# SCH_Capstone_2024-02-12.net
KiCad netlist of a schematic drawn in EasyEDA
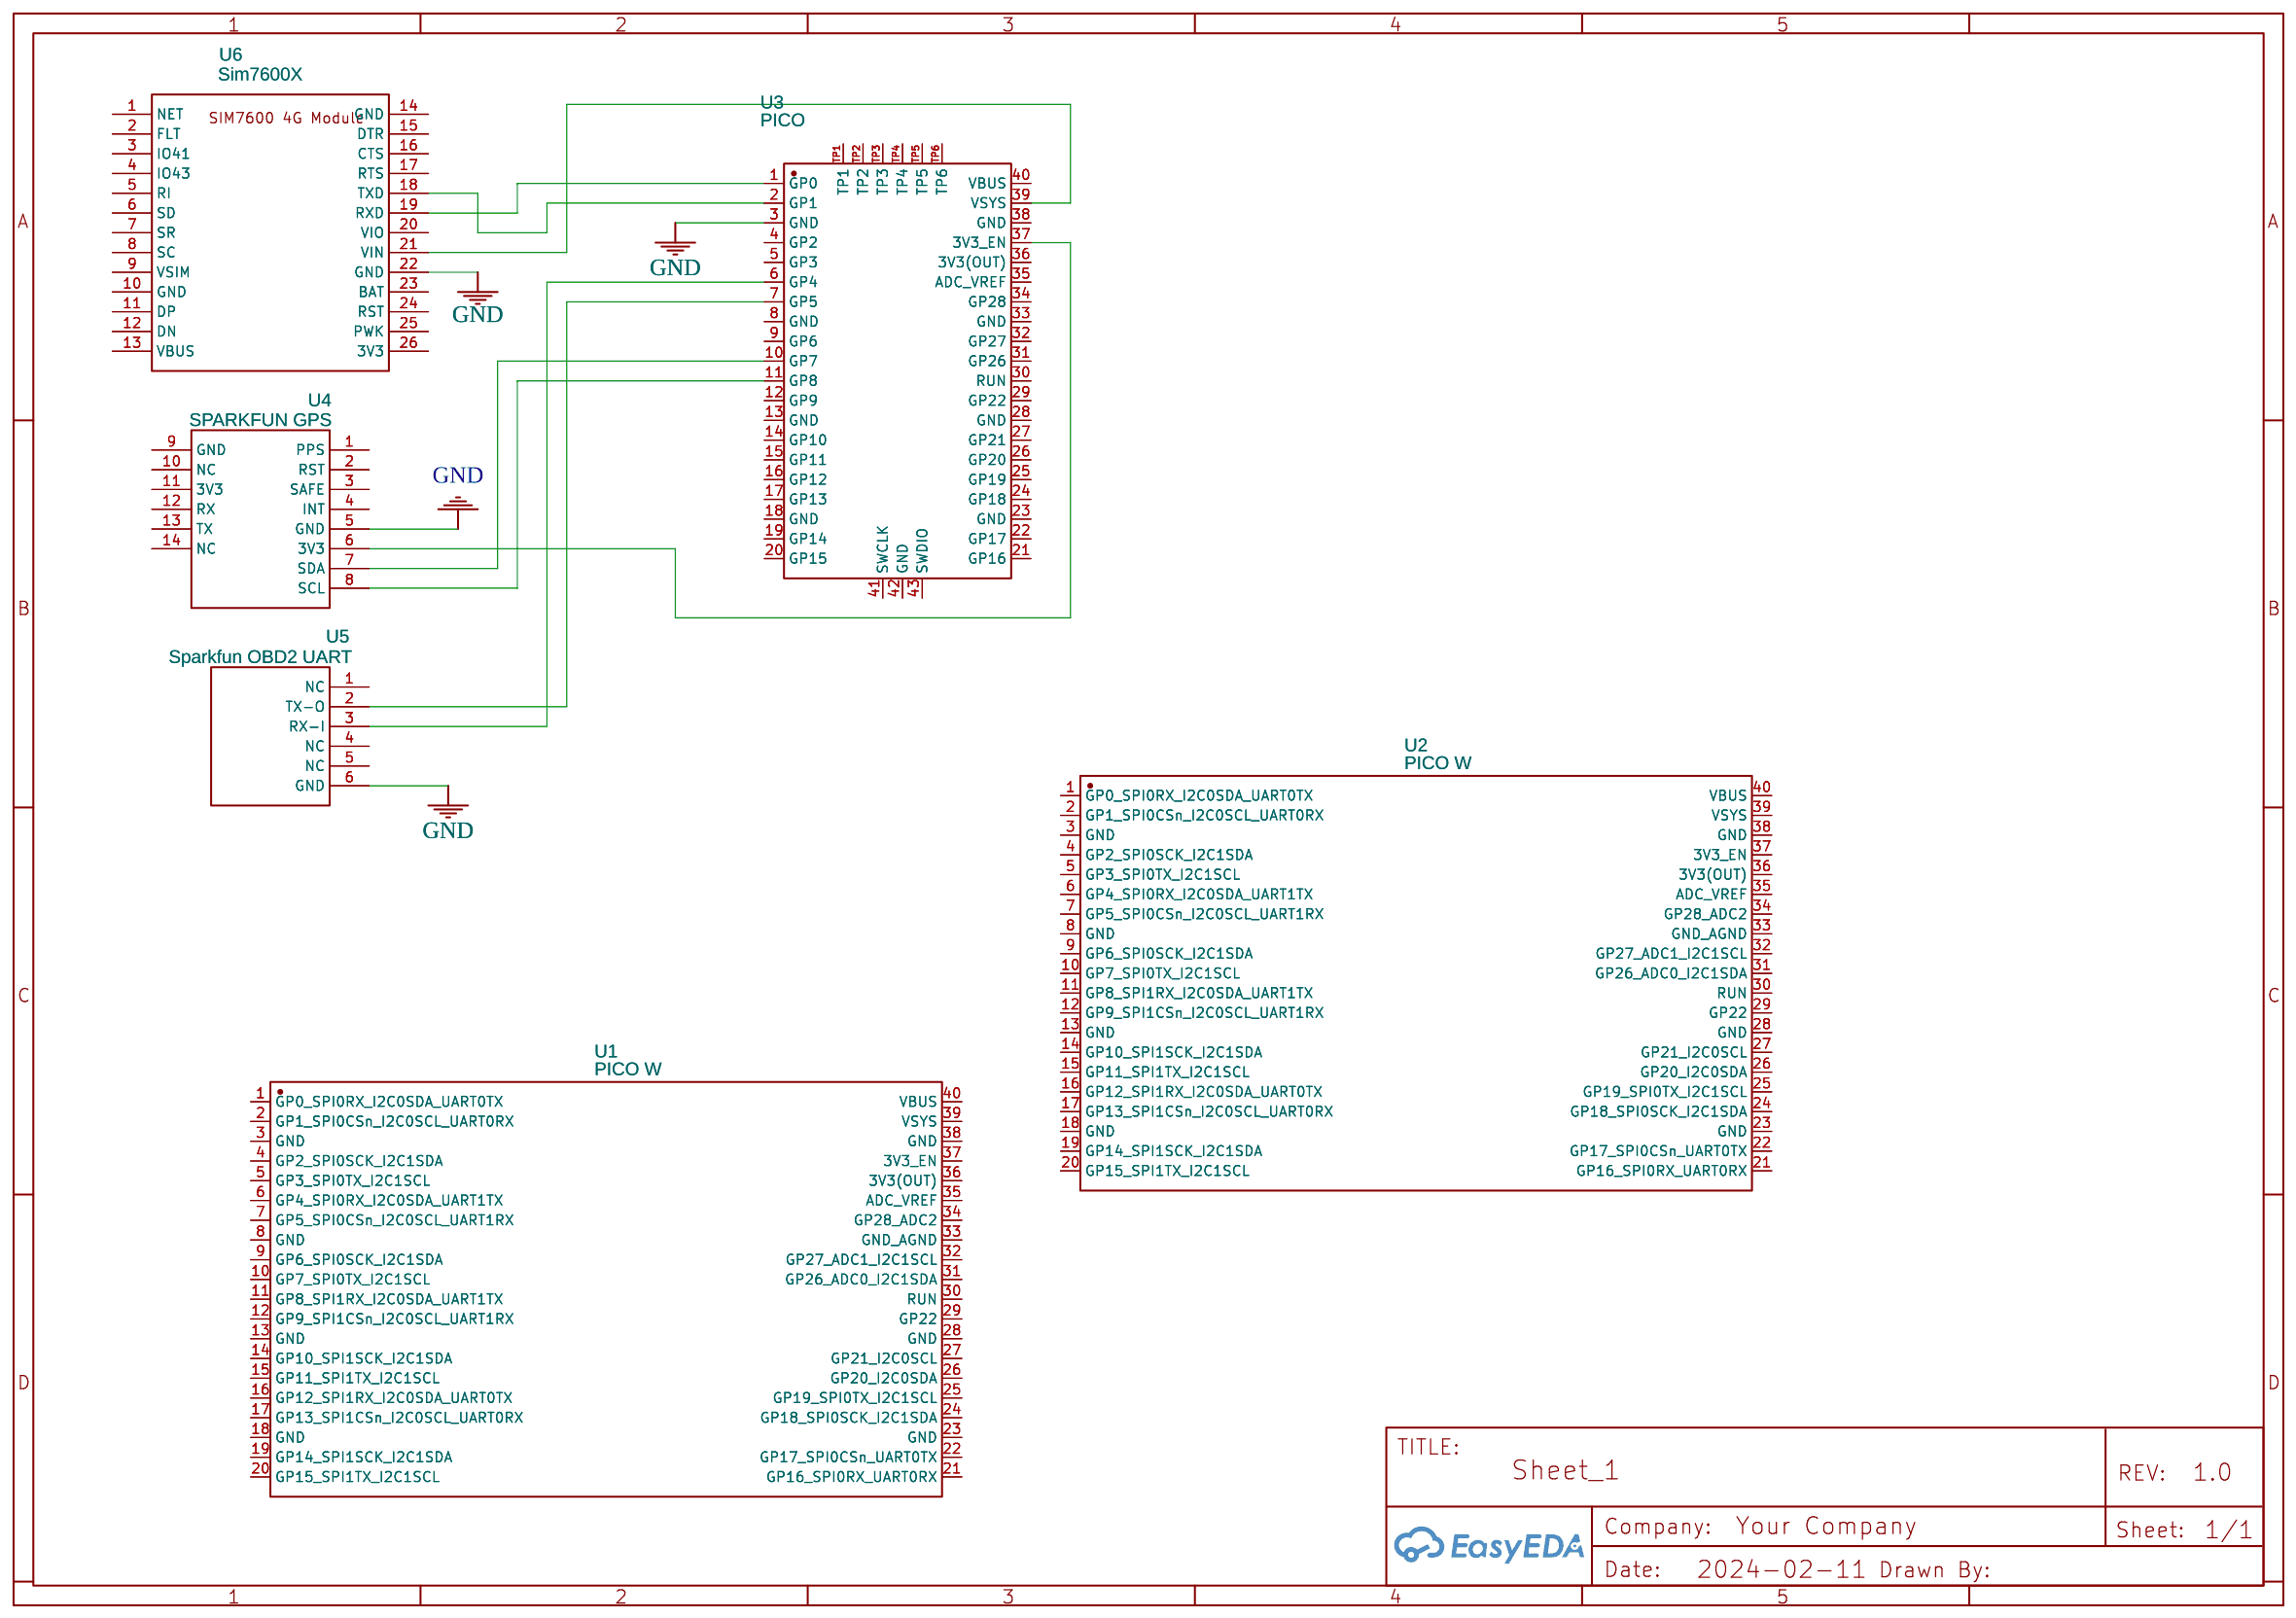
[diagram p0: schematic sheet]

(export (version "E")
  (design (tool "Eeschema 10.0.6"))
  (components
    (comp (ref "U1")
      (value "PICO W")
      (fields (field (name "Manufacturer") "Raspberry Pi(树莓派)"))
      (libsource (lib "") (part "PICO W"))
    )
    (comp (ref "U2")
      (value "PICO W")
      (fields (field (name "Manufacturer") "Raspberry Pi(树莓派)"))
      (libsource (lib "") (part "PICO W"))
    )
    (comp (ref "U3")
      (value "PICO")
      (fields (field (name "Manufacturer") "Raspberry Pi(树莓派)"))
      (libsource (lib "") (part "PICO"))
    )
    (comp (ref "U4") (value "SPARKFUN GPS") (libsource (lib "") (part "SPARKFUN GPS")))
    (comp (ref "U5") (value "Sparkfun OBD2 UART") (libsource (lib "") (part "Sparkfun OBD2 UART")))
    (comp (ref "U6") (value "Sim7600X") (libsource (lib "") (part "Sim7600X")))
  )
  (nets
    (net (code "1") (name "GND") (class "Default")
      (node (ref "U3") (pin "3") (pinfunction "GND_3") (pintype "unspecified"))
      (node (ref "U4") (pin "5") (pinfunction "GND_5") (pintype "unspecified"))
      (node (ref "U5") (pin "6") (pinfunction "GND_6") (pintype "unspecified"))
      (node (ref "U6") (pin "22") (pinfunction "GND_22") (pintype "unspecified"))
    )
    (net (code "2") (name "Net-(U3-3V3_EN)") (class "Default")
      (node (ref "U3") (pin "37") (pinfunction "3V3_EN_37") (pintype "unspecified"))
      (node (ref "U4") (pin "6") (pinfunction "3V3_6") (pintype "unspecified"))
    )
    (net (code "3") (name "Net-(U3-GP0)") (class "Default")
      (node (ref "U3") (pin "1") (pinfunction "GP0_1") (pintype "unspecified"))
      (node (ref "U6") (pin "19") (pinfunction "RXD_19") (pintype "unspecified"))
    )
    (net (code "4") (name "Net-(U3-GP1)") (class "Default")
      (node (ref "U3") (pin "2") (pinfunction "GP1_2") (pintype "unspecified"))
      (node (ref "U6") (pin "18") (pinfunction "TXD_18") (pintype "unspecified"))
    )
    (net (code "5") (name "Net-(U3-GP4)") (class "Default")
      (node (ref "U3") (pin "6") (pinfunction "GP4_6") (pintype "unspecified"))
      (node (ref "U5") (pin "3") (pinfunction "RX-I_3") (pintype "unspecified"))
    )
    (net (code "6") (name "Net-(U3-GP5)") (class "Default")
      (node (ref "U3") (pin "7") (pinfunction "GP5_7") (pintype "unspecified"))
      (node (ref "U5") (pin "2") (pinfunction "TX-O_2") (pintype "unspecified"))
    )
    (net (code "7") (name "Net-(U3-GP7)") (class "Default")
      (node (ref "U3") (pin "10") (pinfunction "GP7_10") (pintype "unspecified"))
      (node (ref "U4") (pin "7") (pinfunction "SDA_7") (pintype "unspecified"))
    )
    (net (code "8") (name "Net-(U3-GP8)") (class "Default")
      (node (ref "U3") (pin "11") (pinfunction "GP8_11") (pintype "unspecified"))
      (node (ref "U4") (pin "8") (pinfunction "SCL_8") (pintype "unspecified"))
    )
    (net (code "9") (name "Net-(U3-VSYS)") (class "Default")
      (node (ref "U3") (pin "39") (pinfunction "VSYS_39") (pintype "unspecified"))
      (node (ref "U6") (pin "21") (pinfunction "VIN_21") (pintype "unspecified"))
    )
    (net (code "10") (name "unconnected-(U1-3V3(OUT)-Pad36)") (class "Default")
      (node (ref "U1") (pin "36") (pinfunction "3V3(OUT)_36") (pintype "unspecified"))
    )
    (net (code "11") (name "unconnected-(U1-3V3_EN-Pad37)") (class "Default")
      (node (ref "U1") (pin "37") (pinfunction "3V3_EN_37") (pintype "unspecified"))
    )
    (net (code "12") (name "unconnected-(U1-ADC_VREF-Pad35)") (class "Default")
      (node (ref "U1") (pin "35") (pinfunction "ADC_VREF_35") (pintype "unspecified"))
    )
    (net (code "13") (name "unconnected-(U1-GND-Pad3)") (class "Default")
      (node (ref "U1") (pin "3") (pinfunction "GND_3") (pintype "unspecified"))
    )
    (net (code "14") (name "unconnected-(U1-GND-Pad8)") (class "Default")
      (node (ref "U1") (pin "8") (pinfunction "GND_8") (pintype "unspecified"))
    )
    (net (code "15") (name "unconnected-(U1-GND-Pad13)") (class "Default")
      (node (ref "U1") (pin "13") (pinfunction "GND_13") (pintype "unspecified"))
    )
    (net (code "16") (name "unconnected-(U1-GND-Pad18)") (class "Default")
      (node (ref "U1") (pin "18") (pinfunction "GND_18") (pintype "unspecified"))
    )
    (net (code "17") (name "unconnected-(U1-GND-Pad23)") (class "Default")
      (node (ref "U1") (pin "23") (pinfunction "GND_23") (pintype "unspecified"))
    )
    (net (code "18") (name "unconnected-(U1-GND-Pad28)") (class "Default")
      (node (ref "U1") (pin "28") (pinfunction "GND_28") (pintype "unspecified"))
    )
    (net (code "19") (name "unconnected-(U1-GND-Pad38)") (class "Default")
      (node (ref "U1") (pin "38") (pinfunction "GND_38") (pintype "unspecified"))
    )
    (net (code "20") (name "unconnected-(U1-GND_AGND-Pad33)") (class "Default")
      (node (ref "U1") (pin "33") (pinfunction "GND_AGND_33") (pintype "unspecified"))
    )
    (net (code "21") (name "unconnected-(U1-GP0_SPI0RX_I2C0SDA_UART0TX-Pad1)") (class "Default")
      (node (ref "U1") (pin "1") (pinfunction "GP0_SPI0RX_I2C0SDA_UART0TX_1") (pintype "unspecified"))
    )
    (net (code "22") (name "unconnected-(U1-GP1_SPI0CSn_I2C0SCL_UART0RX-Pad2)") (class "Default")
      (node (ref "U1") (pin "2") (pinfunction "GP1_SPI0CSn_I2C0SCL_UART0RX_2") (pintype "unspecified"))
    )
    (net (code "23") (name "unconnected-(U1-GP2_SPI0SCK_I2C1SDA-Pad4)") (class "Default")
      (node (ref "U1") (pin "4") (pinfunction "GP2_SPI0SCK_I2C1SDA_4") (pintype "unspecified"))
    )
    (net (code "24") (name "unconnected-(U1-GP3_SPI0TX_I2C1SCL-Pad5)") (class "Default")
      (node (ref "U1") (pin "5") (pinfunction "GP3_SPI0TX_I2C1SCL_5") (pintype "unspecified"))
    )
    (net (code "25") (name "unconnected-(U1-GP4_SPI0RX_I2C0SDA_UART1TX-Pad6)") (class "Default")
      (node (ref "U1") (pin "6") (pinfunction "GP4_SPI0RX_I2C0SDA_UART1TX_6") (pintype "unspecified"))
    )
    (net (code "26") (name "unconnected-(U1-GP5_SPI0CSn_I2C0SCL_UART1RX-Pad7)") (class "Default")
      (node (ref "U1") (pin "7") (pinfunction "GP5_SPI0CSn_I2C0SCL_UART1RX_7") (pintype "unspecified"))
    )
    (net (code "27") (name "unconnected-(U1-GP6_SPI0SCK_I2C1SDA-Pad9)") (class "Default")
      (node (ref "U1") (pin "9") (pinfunction "GP6_SPI0SCK_I2C1SDA_9") (pintype "unspecified"))
    )
    (net (code "28") (name "unconnected-(U1-GP7_SPI0TX_I2C1SCL-Pad10)") (class "Default")
      (node (ref "U1") (pin "10") (pinfunction "GP7_SPI0TX_I2C1SCL_10") (pintype "unspecified"))
    )
    (net (code "29") (name "unconnected-(U1-GP8_SPI1RX_I2C0SDA_UART1TX-Pad11)") (class "Default")
      (node (ref "U1") (pin "11") (pinfunction "GP8_SPI1RX_I2C0SDA_UART1TX_11") (pintype "unspecified"))
    )
    (net (code "30") (name "unconnected-(U1-GP9_SPI1CSn_I2C0SCL_UART1RX-Pad12)") (class "Default")
      (node (ref "U1") (pin "12") (pinfunction "GP9_SPI1CSn_I2C0SCL_UART1RX_12") (pintype "unspecified"))
    )
    (net (code "31") (name "unconnected-(U1-GP10_SPI1SCK_I2C1SDA-Pad14)") (class "Default")
      (node (ref "U1") (pin "14") (pinfunction "GP10_SPI1SCK_I2C1SDA_14") (pintype "unspecified"))
    )
    (net (code "32") (name "unconnected-(U1-GP11_SPI1TX_I2C1SCL-Pad15)") (class "Default")
      (node (ref "U1") (pin "15") (pinfunction "GP11_SPI1TX_I2C1SCL_15") (pintype "unspecified"))
    )
    (net (code "33") (name "unconnected-(U1-GP12_SPI1RX_I2C0SDA_UART0TX-Pad16)") (class "Default")
      (node (ref "U1") (pin "16") (pinfunction "GP12_SPI1RX_I2C0SDA_UART0TX_16") (pintype "unspecified"))
    )
    (net (code "34") (name "unconnected-(U1-GP13_SPI1CSn_I2C0SCL_UART0RX-Pad17)") (class "Default")
      (node (ref "U1") (pin "17") (pinfunction "GP13_SPI1CSn_I2C0SCL_UART0RX_17") (pintype "unspecified"))
    )
    (net (code "35") (name "unconnected-(U1-GP14_SPI1SCK_I2C1SDA-Pad19)") (class "Default")
      (node (ref "U1") (pin "19") (pinfunction "GP14_SPI1SCK_I2C1SDA_19") (pintype "unspecified"))
    )
    (net (code "36") (name "unconnected-(U1-GP15_SPI1TX_I2C1SCL-Pad20)") (class "Default")
      (node (ref "U1") (pin "20") (pinfunction "GP15_SPI1TX_I2C1SCL_20") (pintype "unspecified"))
    )
    (net (code "37") (name "unconnected-(U1-GP16_SPI0RX_UART0RX-Pad21)") (class "Default")
      (node (ref "U1") (pin "21") (pinfunction "GP16_SPI0RX_UART0RX_21") (pintype "unspecified"))
    )
    (net (code "38") (name "unconnected-(U1-GP17_SPI0CSn_UART0TX-Pad22)") (class "Default")
      (node (ref "U1") (pin "22") (pinfunction "GP17_SPI0CSn_UART0TX_22") (pintype "unspecified"))
    )
    (net (code "39") (name "unconnected-(U1-GP18_SPI0SCK_I2C1SDA-Pad24)") (class "Default")
      (node (ref "U1") (pin "24") (pinfunction "GP18_SPI0SCK_I2C1SDA_24") (pintype "unspecified"))
    )
    (net (code "40") (name "unconnected-(U1-GP19_SPI0TX_I2C1SCL-Pad25)") (class "Default")
      (node (ref "U1") (pin "25") (pinfunction "GP19_SPI0TX_I2C1SCL_25") (pintype "unspecified"))
    )
    (net (code "41") (name "unconnected-(U1-GP20_I2C0SDA-Pad26)") (class "Default")
      (node (ref "U1") (pin "26") (pinfunction "GP20_I2C0SDA_26") (pintype "unspecified"))
    )
    (net (code "42") (name "unconnected-(U1-GP21_I2C0SCL-Pad27)") (class "Default")
      (node (ref "U1") (pin "27") (pinfunction "GP21_I2C0SCL_27") (pintype "unspecified"))
    )
    (net (code "43") (name "unconnected-(U1-GP22-Pad29)") (class "Default")
      (node (ref "U1") (pin "29") (pinfunction "GP22_29") (pintype "unspecified"))
    )
    (net (code "44") (name "unconnected-(U1-GP26_ADC0_I2C1SDA-Pad31)") (class "Default")
      (node (ref "U1") (pin "31") (pinfunction "GP26_ADC0_I2C1SDA_31") (pintype "unspecified"))
    )
    (net (code "45") (name "unconnected-(U1-GP27_ADC1_I2C1SCL-Pad32)") (class "Default")
      (node (ref "U1") (pin "32") (pinfunction "GP27_ADC1_I2C1SCL_32") (pintype "unspecified"))
    )
    (net (code "46") (name "unconnected-(U1-GP28_ADC2-Pad34)") (class "Default")
      (node (ref "U1") (pin "34") (pinfunction "GP28_ADC2_34") (pintype "unspecified"))
    )
    (net (code "47") (name "unconnected-(U1-RUN-Pad30)") (class "Default")
      (node (ref "U1") (pin "30") (pinfunction "RUN_30") (pintype "unspecified"))
    )
    (net (code "48") (name "unconnected-(U1-VBUS-Pad40)") (class "Default")
      (node (ref "U1") (pin "40") (pinfunction "VBUS_40") (pintype "unspecified"))
    )
    (net (code "49") (name "unconnected-(U1-VSYS-Pad39)") (class "Default")
      (node (ref "U1") (pin "39") (pinfunction "VSYS_39") (pintype "unspecified"))
    )
    (net (code "50") (name "unconnected-(U2-3V3(OUT)-Pad36)") (class "Default")
      (node (ref "U2") (pin "36") (pinfunction "3V3(OUT)_36") (pintype "unspecified"))
    )
    (net (code "51") (name "unconnected-(U2-3V3_EN-Pad37)") (class "Default")
      (node (ref "U2") (pin "37") (pinfunction "3V3_EN_37") (pintype "unspecified"))
    )
    (net (code "52") (name "unconnected-(U2-ADC_VREF-Pad35)") (class "Default")
      (node (ref "U2") (pin "35") (pinfunction "ADC_VREF_35") (pintype "unspecified"))
    )
    (net (code "53") (name "unconnected-(U2-GND-Pad3)") (class "Default")
      (node (ref "U2") (pin "3") (pinfunction "GND_3") (pintype "unspecified"))
    )
    (net (code "54") (name "unconnected-(U2-GND-Pad8)") (class "Default")
      (node (ref "U2") (pin "8") (pinfunction "GND_8") (pintype "unspecified"))
    )
    (net (code "55") (name "unconnected-(U2-GND-Pad13)") (class "Default")
      (node (ref "U2") (pin "13") (pinfunction "GND_13") (pintype "unspecified"))
    )
    (net (code "56") (name "unconnected-(U2-GND-Pad18)") (class "Default")
      (node (ref "U2") (pin "18") (pinfunction "GND_18") (pintype "unspecified"))
    )
    (net (code "57") (name "unconnected-(U2-GND-Pad23)") (class "Default")
      (node (ref "U2") (pin "23") (pinfunction "GND_23") (pintype "unspecified"))
    )
    (net (code "58") (name "unconnected-(U2-GND-Pad28)") (class "Default")
      (node (ref "U2") (pin "28") (pinfunction "GND_28") (pintype "unspecified"))
    )
    (net (code "59") (name "unconnected-(U2-GND-Pad38)") (class "Default")
      (node (ref "U2") (pin "38") (pinfunction "GND_38") (pintype "unspecified"))
    )
    (net (code "60") (name "unconnected-(U2-GND_AGND-Pad33)") (class "Default")
      (node (ref "U2") (pin "33") (pinfunction "GND_AGND_33") (pintype "unspecified"))
    )
    (net (code "61") (name "unconnected-(U2-GP0_SPI0RX_I2C0SDA_UART0TX-Pad1)") (class "Default")
      (node (ref "U2") (pin "1") (pinfunction "GP0_SPI0RX_I2C0SDA_UART0TX_1") (pintype "unspecified"))
    )
    (net (code "62") (name "unconnected-(U2-GP1_SPI0CSn_I2C0SCL_UART0RX-Pad2)") (class "Default")
      (node (ref "U2") (pin "2") (pinfunction "GP1_SPI0CSn_I2C0SCL_UART0RX_2") (pintype "unspecified"))
    )
    (net (code "63") (name "unconnected-(U2-GP2_SPI0SCK_I2C1SDA-Pad4)") (class "Default")
      (node (ref "U2") (pin "4") (pinfunction "GP2_SPI0SCK_I2C1SDA_4") (pintype "unspecified"))
    )
    (net (code "64") (name "unconnected-(U2-GP3_SPI0TX_I2C1SCL-Pad5)") (class "Default")
      (node (ref "U2") (pin "5") (pinfunction "GP3_SPI0TX_I2C1SCL_5") (pintype "unspecified"))
    )
    (net (code "65") (name "unconnected-(U2-GP4_SPI0RX_I2C0SDA_UART1TX-Pad6)") (class "Default")
      (node (ref "U2") (pin "6") (pinfunction "GP4_SPI0RX_I2C0SDA_UART1TX_6") (pintype "unspecified"))
    )
    (net (code "66") (name "unconnected-(U2-GP5_SPI0CSn_I2C0SCL_UART1RX-Pad7)") (class "Default")
      (node (ref "U2") (pin "7") (pinfunction "GP5_SPI0CSn_I2C0SCL_UART1RX_7") (pintype "unspecified"))
    )
    (net (code "67") (name "unconnected-(U2-GP6_SPI0SCK_I2C1SDA-Pad9)") (class "Default")
      (node (ref "U2") (pin "9") (pinfunction "GP6_SPI0SCK_I2C1SDA_9") (pintype "unspecified"))
    )
    (net (code "68") (name "unconnected-(U2-GP7_SPI0TX_I2C1SCL-Pad10)") (class "Default")
      (node (ref "U2") (pin "10") (pinfunction "GP7_SPI0TX_I2C1SCL_10") (pintype "unspecified"))
    )
    (net (code "69") (name "unconnected-(U2-GP8_SPI1RX_I2C0SDA_UART1TX-Pad11)") (class "Default")
      (node (ref "U2") (pin "11") (pinfunction "GP8_SPI1RX_I2C0SDA_UART1TX_11") (pintype "unspecified"))
    )
    (net (code "70") (name "unconnected-(U2-GP9_SPI1CSn_I2C0SCL_UART1RX-Pad12)") (class "Default")
      (node (ref "U2") (pin "12") (pinfunction "GP9_SPI1CSn_I2C0SCL_UART1RX_12") (pintype "unspecified"))
    )
    (net (code "71") (name "unconnected-(U2-GP10_SPI1SCK_I2C1SDA-Pad14)") (class "Default")
      (node (ref "U2") (pin "14") (pinfunction "GP10_SPI1SCK_I2C1SDA_14") (pintype "unspecified"))
    )
    (net (code "72") (name "unconnected-(U2-GP11_SPI1TX_I2C1SCL-Pad15)") (class "Default")
      (node (ref "U2") (pin "15") (pinfunction "GP11_SPI1TX_I2C1SCL_15") (pintype "unspecified"))
    )
    (net (code "73") (name "unconnected-(U2-GP12_SPI1RX_I2C0SDA_UART0TX-Pad16)") (class "Default")
      (node (ref "U2") (pin "16") (pinfunction "GP12_SPI1RX_I2C0SDA_UART0TX_16") (pintype "unspecified"))
    )
    (net (code "74") (name "unconnected-(U2-GP13_SPI1CSn_I2C0SCL_UART0RX-Pad17)") (class "Default")
      (node (ref "U2") (pin "17") (pinfunction "GP13_SPI1CSn_I2C0SCL_UART0RX_17") (pintype "unspecified"))
    )
    (net (code "75") (name "unconnected-(U2-GP14_SPI1SCK_I2C1SDA-Pad19)") (class "Default")
      (node (ref "U2") (pin "19") (pinfunction "GP14_SPI1SCK_I2C1SDA_19") (pintype "unspecified"))
    )
    (net (code "76") (name "unconnected-(U2-GP15_SPI1TX_I2C1SCL-Pad20)") (class "Default")
      (node (ref "U2") (pin "20") (pinfunction "GP15_SPI1TX_I2C1SCL_20") (pintype "unspecified"))
    )
    (net (code "77") (name "unconnected-(U2-GP16_SPI0RX_UART0RX-Pad21)") (class "Default")
      (node (ref "U2") (pin "21") (pinfunction "GP16_SPI0RX_UART0RX_21") (pintype "unspecified"))
    )
    (net (code "78") (name "unconnected-(U2-GP17_SPI0CSn_UART0TX-Pad22)") (class "Default")
      (node (ref "U2") (pin "22") (pinfunction "GP17_SPI0CSn_UART0TX_22") (pintype "unspecified"))
    )
    (net (code "79") (name "unconnected-(U2-GP18_SPI0SCK_I2C1SDA-Pad24)") (class "Default")
      (node (ref "U2") (pin "24") (pinfunction "GP18_SPI0SCK_I2C1SDA_24") (pintype "unspecified"))
    )
    (net (code "80") (name "unconnected-(U2-GP19_SPI0TX_I2C1SCL-Pad25)") (class "Default")
      (node (ref "U2") (pin "25") (pinfunction "GP19_SPI0TX_I2C1SCL_25") (pintype "unspecified"))
    )
    (net (code "81") (name "unconnected-(U2-GP20_I2C0SDA-Pad26)") (class "Default")
      (node (ref "U2") (pin "26") (pinfunction "GP20_I2C0SDA_26") (pintype "unspecified"))
    )
    (net (code "82") (name "unconnected-(U2-GP21_I2C0SCL-Pad27)") (class "Default")
      (node (ref "U2") (pin "27") (pinfunction "GP21_I2C0SCL_27") (pintype "unspecified"))
    )
    (net (code "83") (name "unconnected-(U2-GP22-Pad29)") (class "Default")
      (node (ref "U2") (pin "29") (pinfunction "GP22_29") (pintype "unspecified"))
    )
    (net (code "84") (name "unconnected-(U2-GP26_ADC0_I2C1SDA-Pad31)") (class "Default")
      (node (ref "U2") (pin "31") (pinfunction "GP26_ADC0_I2C1SDA_31") (pintype "unspecified"))
    )
    (net (code "85") (name "unconnected-(U2-GP27_ADC1_I2C1SCL-Pad32)") (class "Default")
      (node (ref "U2") (pin "32") (pinfunction "GP27_ADC1_I2C1SCL_32") (pintype "unspecified"))
    )
    (net (code "86") (name "unconnected-(U2-GP28_ADC2-Pad34)") (class "Default")
      (node (ref "U2") (pin "34") (pinfunction "GP28_ADC2_34") (pintype "unspecified"))
    )
    (net (code "87") (name "unconnected-(U2-RUN-Pad30)") (class "Default")
      (node (ref "U2") (pin "30") (pinfunction "RUN_30") (pintype "unspecified"))
    )
    (net (code "88") (name "unconnected-(U2-VBUS-Pad40)") (class "Default")
      (node (ref "U2") (pin "40") (pinfunction "VBUS_40") (pintype "unspecified"))
    )
    (net (code "89") (name "unconnected-(U2-VSYS-Pad39)") (class "Default")
      (node (ref "U2") (pin "39") (pinfunction "VSYS_39") (pintype "unspecified"))
    )
    (net (code "90") (name "unconnected-(U3-3V3(OUT)-Pad36)") (class "Default")
      (node (ref "U3") (pin "36") (pinfunction "3V3(OUT)_36") (pintype "unspecified"))
    )
    (net (code "91") (name "unconnected-(U3-ADC_VREF-Pad35)") (class "Default")
      (node (ref "U3") (pin "35") (pinfunction "ADC_VREF_35") (pintype "unspecified"))
    )
    (net (code "92") (name "unconnected-(U3-GND-Pad8)") (class "Default")
      (node (ref "U3") (pin "8") (pinfunction "GND_8") (pintype "unspecified"))
    )
    (net (code "93") (name "unconnected-(U3-GND-Pad13)") (class "Default")
      (node (ref "U3") (pin "13") (pinfunction "GND_13") (pintype "unspecified"))
    )
    (net (code "94") (name "unconnected-(U3-GND-Pad18)") (class "Default")
      (node (ref "U3") (pin "18") (pinfunction "GND_18") (pintype "unspecified"))
    )
    (net (code "95") (name "unconnected-(U3-GND-Pad23)") (class "Default")
      (node (ref "U3") (pin "23") (pinfunction "GND_23") (pintype "unspecified"))
    )
    (net (code "96") (name "unconnected-(U3-GND-Pad28)") (class "Default")
      (node (ref "U3") (pin "28") (pinfunction "GND_28") (pintype "unspecified"))
    )
    (net (code "97") (name "unconnected-(U3-GND-Pad33)") (class "Default")
      (node (ref "U3") (pin "33") (pinfunction "GND_33") (pintype "unspecified"))
    )
    (net (code "98") (name "unconnected-(U3-GND-Pad38)") (class "Default")
      (node (ref "U3") (pin "38") (pinfunction "GND_38") (pintype "unspecified"))
    )
    (net (code "99") (name "unconnected-(U3-GND-Pad42)") (class "Default")
      (node (ref "U3") (pin "42") (pinfunction "GND_42") (pintype "unspecified"))
    )
    (net (code "100") (name "unconnected-(U3-GP2-Pad4)") (class "Default")
      (node (ref "U3") (pin "4") (pinfunction "GP2_4") (pintype "unspecified"))
    )
    (net (code "101") (name "unconnected-(U3-GP3-Pad5)") (class "Default")
      (node (ref "U3") (pin "5") (pinfunction "GP3_5") (pintype "unspecified"))
    )
    (net (code "102") (name "unconnected-(U3-GP6-Pad9)") (class "Default")
      (node (ref "U3") (pin "9") (pinfunction "GP6_9") (pintype "unspecified"))
    )
    (net (code "103") (name "unconnected-(U3-GP9-Pad12)") (class "Default")
      (node (ref "U3") (pin "12") (pinfunction "GP9_12") (pintype "unspecified"))
    )
    (net (code "104") (name "unconnected-(U3-GP10-Pad14)") (class "Default")
      (node (ref "U3") (pin "14") (pinfunction "GP10_14") (pintype "unspecified"))
    )
    (net (code "105") (name "unconnected-(U3-GP11-Pad15)") (class "Default")
      (node (ref "U3") (pin "15") (pinfunction "GP11_15") (pintype "unspecified"))
    )
    (net (code "106") (name "unconnected-(U3-GP12-Pad16)") (class "Default")
      (node (ref "U3") (pin "16") (pinfunction "GP12_16") (pintype "unspecified"))
    )
    (net (code "107") (name "unconnected-(U3-GP13-Pad17)") (class "Default")
      (node (ref "U3") (pin "17") (pinfunction "GP13_17") (pintype "unspecified"))
    )
    (net (code "108") (name "unconnected-(U3-GP14-Pad19)") (class "Default")
      (node (ref "U3") (pin "19") (pinfunction "GP14_19") (pintype "unspecified"))
    )
    (net (code "109") (name "unconnected-(U3-GP15-Pad20)") (class "Default")
      (node (ref "U3") (pin "20") (pinfunction "GP15_20") (pintype "unspecified"))
    )
    (net (code "110") (name "unconnected-(U3-GP16-Pad21)") (class "Default")
      (node (ref "U3") (pin "21") (pinfunction "GP16_21") (pintype "unspecified"))
    )
    (net (code "111") (name "unconnected-(U3-GP17-Pad22)") (class "Default")
      (node (ref "U3") (pin "22") (pinfunction "GP17_22") (pintype "unspecified"))
    )
    (net (code "112") (name "unconnected-(U3-GP18-Pad24)") (class "Default")
      (node (ref "U3") (pin "24") (pinfunction "GP18_24") (pintype "unspecified"))
    )
    (net (code "113") (name "unconnected-(U3-GP19-Pad25)") (class "Default")
      (node (ref "U3") (pin "25") (pinfunction "GP19_25") (pintype "unspecified"))
    )
    (net (code "114") (name "unconnected-(U3-GP20-Pad26)") (class "Default")
      (node (ref "U3") (pin "26") (pinfunction "GP20_26") (pintype "unspecified"))
    )
    (net (code "115") (name "unconnected-(U3-GP21-Pad27)") (class "Default")
      (node (ref "U3") (pin "27") (pinfunction "GP21_27") (pintype "unspecified"))
    )
    (net (code "116") (name "unconnected-(U3-GP22-Pad29)") (class "Default")
      (node (ref "U3") (pin "29") (pinfunction "GP22_29") (pintype "unspecified"))
    )
    (net (code "117") (name "unconnected-(U3-GP26-Pad31)") (class "Default")
      (node (ref "U3") (pin "31") (pinfunction "GP26_31") (pintype "unspecified"))
    )
    (net (code "118") (name "unconnected-(U3-GP27-Pad32)") (class "Default")
      (node (ref "U3") (pin "32") (pinfunction "GP27_32") (pintype "unspecified"))
    )
    (net (code "119") (name "unconnected-(U3-GP28-Pad34)") (class "Default")
      (node (ref "U3") (pin "34") (pinfunction "GP28_34") (pintype "unspecified"))
    )
    (net (code "120") (name "unconnected-(U3-PadTP1)") (class "Default")
      (node (ref "U3") (pin "TP1") (pinfunction "TP1_TP1") (pintype "unspecified"))
    )
    (net (code "121") (name "unconnected-(U3-PadTP2)") (class "Default")
      (node (ref "U3") (pin "TP2") (pinfunction "TP2_TP2") (pintype "unspecified"))
    )
    (net (code "122") (name "unconnected-(U3-PadTP3)") (class "Default")
      (node (ref "U3") (pin "TP3") (pinfunction "TP3_TP3") (pintype "unspecified"))
    )
    (net (code "123") (name "unconnected-(U3-PadTP4)") (class "Default")
      (node (ref "U3") (pin "TP4") (pinfunction "TP4_TP4") (pintype "unspecified"))
    )
    (net (code "124") (name "unconnected-(U3-PadTP5)") (class "Default")
      (node (ref "U3") (pin "TP5") (pinfunction "TP5_TP5") (pintype "unspecified"))
    )
    (net (code "125") (name "unconnected-(U3-PadTP6)") (class "Default")
      (node (ref "U3") (pin "TP6") (pinfunction "TP6_TP6") (pintype "unspecified"))
    )
    (net (code "126") (name "unconnected-(U3-RUN-Pad30)") (class "Default")
      (node (ref "U3") (pin "30") (pinfunction "RUN_30") (pintype "unspecified"))
    )
    (net (code "127") (name "unconnected-(U3-SWCLK-Pad41)") (class "Default")
      (node (ref "U3") (pin "41") (pinfunction "SWCLK_41") (pintype "unspecified"))
    )
    (net (code "128") (name "unconnected-(U3-SWDIO-Pad43)") (class "Default")
      (node (ref "U3") (pin "43") (pinfunction "SWDIO_43") (pintype "unspecified"))
    )
    (net (code "129") (name "unconnected-(U3-VBUS-Pad40)") (class "Default")
      (node (ref "U3") (pin "40") (pinfunction "VBUS_40") (pintype "unspecified"))
    )
    (net (code "130") (name "unconnected-(U4-3V3-Pad11)") (class "Default")
      (node (ref "U4") (pin "11") (pinfunction "3V3_11") (pintype "unspecified"))
    )
    (net (code "131") (name "unconnected-(U4-GND-Pad9)") (class "Default")
      (node (ref "U4") (pin "9") (pinfunction "GND_9") (pintype "unspecified"))
    )
    (net (code "132") (name "unconnected-(U4-INT-Pad4)") (class "Default")
      (node (ref "U4") (pin "4") (pinfunction "INT_4") (pintype "unspecified"))
    )
    (net (code "133") (name "unconnected-(U4-NC-Pad10)") (class "Default")
      (node (ref "U4") (pin "10") (pinfunction "NC_10") (pintype "unspecified"))
    )
    (net (code "134") (name "unconnected-(U4-NC-Pad14)") (class "Default")
      (node (ref "U4") (pin "14") (pinfunction "NC_14") (pintype "unspecified"))
    )
    (net (code "135") (name "unconnected-(U4-PPS-Pad1)") (class "Default")
      (node (ref "U4") (pin "1") (pinfunction "PPS_1") (pintype "unspecified"))
    )
    (net (code "136") (name "unconnected-(U4-RST-Pad2)") (class "Default")
      (node (ref "U4") (pin "2") (pinfunction "RST_2") (pintype "unspecified"))
    )
    (net (code "137") (name "unconnected-(U4-RX-Pad12)") (class "Default")
      (node (ref "U4") (pin "12") (pinfunction "RX_12") (pintype "unspecified"))
    )
    (net (code "138") (name "unconnected-(U4-SAFE-Pad3)") (class "Default")
      (node (ref "U4") (pin "3") (pinfunction "SAFE_3") (pintype "unspecified"))
    )
    (net (code "139") (name "unconnected-(U4-TX-Pad13)") (class "Default")
      (node (ref "U4") (pin "13") (pinfunction "TX_13") (pintype "unspecified"))
    )
    (net (code "140") (name "unconnected-(U5-NC-Pad1)") (class "Default")
      (node (ref "U5") (pin "1") (pinfunction "NC_1") (pintype "unspecified"))
    )
    (net (code "141") (name "unconnected-(U5-NC-Pad4)") (class "Default")
      (node (ref "U5") (pin "4") (pinfunction "NC_4") (pintype "unspecified"))
    )
    (net (code "142") (name "unconnected-(U5-NC-Pad5)") (class "Default")
      (node (ref "U5") (pin "5") (pinfunction "NC_5") (pintype "unspecified"))
    )
    (net (code "143") (name "unconnected-(U6-3V3-Pad26)") (class "Default")
      (node (ref "U6") (pin "26") (pinfunction "3V3_26") (pintype "unspecified"))
    )
    (net (code "144") (name "unconnected-(U6-BAT-Pad23)") (class "Default")
      (node (ref "U6") (pin "23") (pinfunction "BAT_23") (pintype "unspecified"))
    )
    (net (code "145") (name "unconnected-(U6-CTS-Pad16)") (class "Default")
      (node (ref "U6") (pin "16") (pinfunction "CTS_16") (pintype "unspecified"))
    )
    (net (code "146") (name "unconnected-(U6-DN-Pad12)") (class "Default")
      (node (ref "U6") (pin "12") (pinfunction "DN_12") (pintype "unspecified"))
    )
    (net (code "147") (name "unconnected-(U6-DP-Pad11)") (class "Default")
      (node (ref "U6") (pin "11") (pinfunction "DP_11") (pintype "unspecified"))
    )
    (net (code "148") (name "unconnected-(U6-DTR-Pad15)") (class "Default")
      (node (ref "U6") (pin "15") (pinfunction "DTR_15") (pintype "unspecified"))
    )
    (net (code "149") (name "unconnected-(U6-FLT-Pad2)") (class "Default")
      (node (ref "U6") (pin "2") (pinfunction "FLT_2") (pintype "unspecified"))
    )
    (net (code "150") (name "unconnected-(U6-GND-Pad10)") (class "Default")
      (node (ref "U6") (pin "10") (pinfunction "GND_10") (pintype "unspecified"))
    )
    (net (code "151") (name "unconnected-(U6-GND-Pad14)") (class "Default")
      (node (ref "U6") (pin "14") (pinfunction "GND_14") (pintype "unspecified"))
    )
    (net (code "152") (name "unconnected-(U6-IO41-Pad3)") (class "Default")
      (node (ref "U6") (pin "3") (pinfunction "IO41_3") (pintype "unspecified"))
    )
    (net (code "153") (name "unconnected-(U6-IO43-Pad4)") (class "Default")
      (node (ref "U6") (pin "4") (pinfunction "IO43_4") (pintype "unspecified"))
    )
    (net (code "154") (name "unconnected-(U6-NET-Pad1)") (class "Default")
      (node (ref "U6") (pin "1") (pinfunction "NET_1") (pintype "unspecified"))
    )
    (net (code "155") (name "unconnected-(U6-PWK-Pad25)") (class "Default")
      (node (ref "U6") (pin "25") (pinfunction "PWK_25") (pintype "unspecified"))
    )
    (net (code "156") (name "unconnected-(U6-RI-Pad5)") (class "Default")
      (node (ref "U6") (pin "5") (pinfunction "RI_5") (pintype "unspecified"))
    )
    (net (code "157") (name "unconnected-(U6-RST-Pad24)") (class "Default")
      (node (ref "U6") (pin "24") (pinfunction "RST_24") (pintype "unspecified"))
    )
    (net (code "158") (name "unconnected-(U6-RTS-Pad17)") (class "Default")
      (node (ref "U6") (pin "17") (pinfunction "RTS_17") (pintype "unspecified"))
    )
    (net (code "159") (name "unconnected-(U6-SC-Pad8)") (class "Default")
      (node (ref "U6") (pin "8") (pinfunction "SC_8") (pintype "unspecified"))
    )
    (net (code "160") (name "unconnected-(U6-SD-Pad6)") (class "Default")
      (node (ref "U6") (pin "6") (pinfunction "SD_6") (pintype "unspecified"))
    )
    (net (code "161") (name "unconnected-(U6-SR-Pad7)") (class "Default")
      (node (ref "U6") (pin "7") (pinfunction "SR_7") (pintype "unspecified"))
    )
    (net (code "162") (name "unconnected-(U6-VBUS-Pad13)") (class "Default")
      (node (ref "U6") (pin "13") (pinfunction "VBUS_13") (pintype "unspecified"))
    )
    (net (code "163") (name "unconnected-(U6-VIO-Pad20)") (class "Default")
      (node (ref "U6") (pin "20") (pinfunction "VIO_20") (pintype "unspecified"))
    )
    (net (code "164") (name "unconnected-(U6-VSIM-Pad9)") (class "Default")
      (node (ref "U6") (pin "9") (pinfunction "VSIM_9") (pintype "unspecified"))
    )
  )
)
